# Grove_-_Base_Shield_for_IOIO-OTG.net
KiCad netlist of a schematic drawn in EAGLE
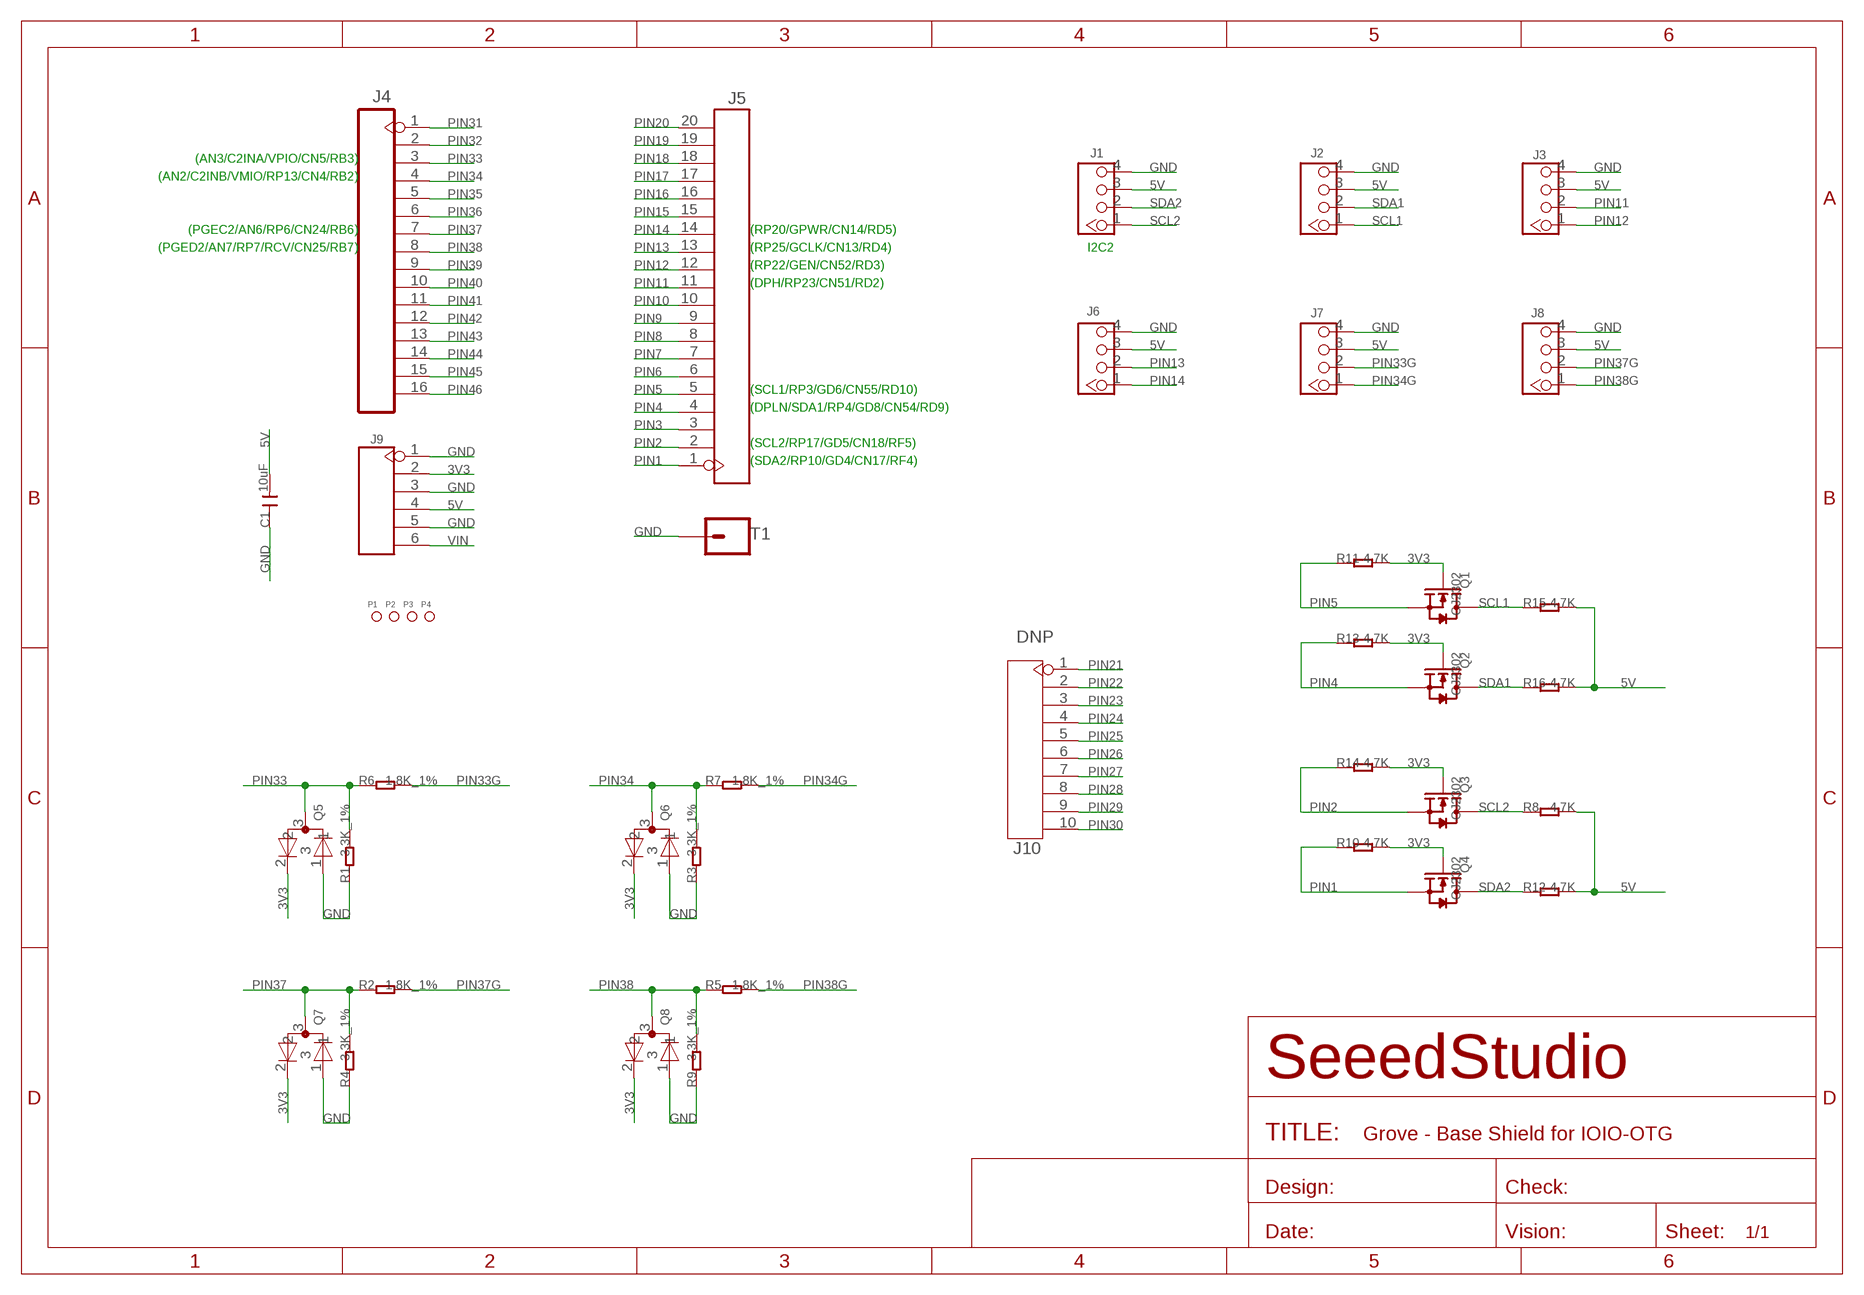
[diagram p0: schematic, sheet 1]

(export (version "E")
  (design (tool "Eeschema 10.0.6"))
  (components
    (comp (ref "C1")
      (value "10uF")
      (footprint "eagle-import:C0805")
      (libsource (lib "eagle-import") (part "C-0805"))
    )
    (comp (ref "J1")
      (value "TWIG-4P-2.0-2.0")
      (footprint "eagle-import:4P-2.0")
      (libsource (lib "eagle-import") (part "TWIG-4P-2.0-2.0"))
    )
    (comp (ref "J2")
      (value "TWIG-4P-2.0-2.0")
      (footprint "eagle-import:4P-2.0")
      (libsource (lib "eagle-import") (part "TWIG-4P-2.0-2.0"))
    )
    (comp (ref "J3")
      (value "TWIG-4P-2.0-2.0")
      (footprint "eagle-import:4P-2.0")
      (libsource (lib "eagle-import") (part "TWIG-4P-2.0-2.0"))
    )
    (comp (ref "J4")
      (value "HEADER-16P-2.54")
      (footprint "eagle-import:16P-2.54")
      (libsource (lib "eagle-import") (part "HEADER-16P-2.54"))
    )
    (comp (ref "J5")
      (value "HEADER-20P-2.54")
      (footprint "eagle-import:20P-2.54")
      (libsource (lib "eagle-import") (part "HEADER-20P-2.54"))
    )
    (comp (ref "J6")
      (value "TWIG-4P-2.0-2.0")
      (footprint "eagle-import:4P-2.0")
      (libsource (lib "eagle-import") (part "TWIG-4P-2.0-2.0"))
    )
    (comp (ref "J7")
      (value "TWIG-4P-2.0-2.0")
      (footprint "eagle-import:4P-2.0")
      (libsource (lib "eagle-import") (part "TWIG-4P-2.0-2.0"))
    )
    (comp (ref "J8")
      (value "TWIG-4P-2.0-2.0")
      (footprint "eagle-import:4P-2.0")
      (libsource (lib "eagle-import") (part "TWIG-4P-2.0-2.0"))
    )
    (comp (ref "J9")
      (value "HEADER-6P-65/35MIL")
      (footprint "eagle-import:6P-2.54-65_35MIL")
      (libsource (lib "eagle-import") (part "HEADER-6P-65/35MIL"))
    )
    (comp (ref "J10")
      (value "DNP")
      (footprint "eagle-import:10P-2.54")
      (libsource (lib "eagle-import") (part "HEADER-10P-2.54"))
    )
    (comp (ref "P1")
      (value "PAD-MARK")
      (footprint "eagle-import:ROUND-MARK-1.0")
      (fields (field (name "PARTNO") "DNP"))
      (libsource (lib "eagle-import") (part "PAD-MARK"))
    )
    (comp (ref "P2")
      (value "PAD-MARK")
      (footprint "eagle-import:ROUND-MARK-1.0")
      (fields (field (name "PARTNO") "DNP"))
      (libsource (lib "eagle-import") (part "PAD-MARK"))
    )
    (comp (ref "P3")
      (value "PAD-MARK")
      (footprint "eagle-import:ROUND-MARK-1.0")
      (fields (field (name "PARTNO") "DNP"))
      (libsource (lib "eagle-import") (part "PAD-MARK"))
    )
    (comp (ref "P4")
      (value "PAD-MARK")
      (footprint "eagle-import:ROUND-MARK-1.0")
      (fields (field (name "PARTNO") "DNP"))
      (libsource (lib "eagle-import") (part "PAD-MARK"))
    )
    (comp (ref "Q1")
      (value "CJ2302")
      (footprint "eagle-import:SOT23")
      (libsource (lib "eagle-import") (part "MOSFET-N'SOT23'"))
    )
    (comp (ref "Q2")
      (value "CJ2302")
      (footprint "eagle-import:SOT23")
      (libsource (lib "eagle-import") (part "MOSFET-N'SOT23'"))
    )
    (comp (ref "Q3")
      (value "CJ2302")
      (footprint "eagle-import:SOT23")
      (libsource (lib "eagle-import") (part "MOSFET-N'SOT23'"))
    )
    (comp (ref "Q4")
      (value "CJ2302")
      (footprint "eagle-import:SOT23")
      (libsource (lib "eagle-import") (part "MOSFET-N'SOT23'"))
    )
    (comp (ref "Q5")
      (value "BAV99")
      (footprint "eagle-import:SOT23")
      (libsource (lib "eagle-import") (part "BAV99"))
    )
    (comp (ref "Q6")
      (value "BAV99")
      (footprint "eagle-import:SOT23")
      (libsource (lib "eagle-import") (part "BAV99"))
    )
    (comp (ref "Q7")
      (value "BAV99")
      (footprint "eagle-import:SOT23")
      (libsource (lib "eagle-import") (part "BAV99"))
    )
    (comp (ref "Q8")
      (value "BAV99")
      (footprint "eagle-import:SOT23")
      (libsource (lib "eagle-import") (part "BAV99"))
    )
    (comp (ref "R1")
      (value "3.3K_1%")
      (footprint "eagle-import:R0603")
      (libsource (lib "eagle-import") (part "R-0603"))
    )
    (comp (ref "R2")
      (value "1.8K_1%")
      (footprint "eagle-import:R0603")
      (libsource (lib "eagle-import") (part "R-0603"))
    )
    (comp (ref "R3")
      (value "3.3K_1%")
      (footprint "eagle-import:R0603")
      (libsource (lib "eagle-import") (part "R-0603"))
    )
    (comp (ref "R4")
      (value "3.3K_1%")
      (footprint "eagle-import:R0603")
      (libsource (lib "eagle-import") (part "R-0603"))
    )
    (comp (ref "R5")
      (value "1.8K_1%")
      (footprint "eagle-import:R0603")
      (libsource (lib "eagle-import") (part "R-0603"))
    )
    (comp (ref "R6")
      (value "1.8K_1%")
      (footprint "eagle-import:R0603")
      (libsource (lib "eagle-import") (part "R-0603"))
    )
    (comp (ref "R7")
      (value "1.8K_1%")
      (footprint "eagle-import:R0603")
      (libsource (lib "eagle-import") (part "R-0603"))
    )
    (comp (ref "R8")
      (value "4.7K")
      (footprint "eagle-import:R0603")
      (libsource (lib "eagle-import") (part "R-0603"))
    )
    (comp (ref "R9")
      (value "3.3K_1%")
      (footprint "eagle-import:R0603")
      (libsource (lib "eagle-import") (part "R-0603"))
    )
    (comp (ref "R10")
      (value "4.7K")
      (footprint "eagle-import:R0603")
      (libsource (lib "eagle-import") (part "R-0603"))
    )
    (comp (ref "R11")
      (value "4.7K")
      (footprint "eagle-import:R0603")
      (libsource (lib "eagle-import") (part "R-0603"))
    )
    (comp (ref "R12")
      (value "4.7K")
      (footprint "eagle-import:R0603")
      (libsource (lib "eagle-import") (part "R-0603"))
    )
    (comp (ref "R13")
      (value "4.7K")
      (footprint "eagle-import:R0603")
      (libsource (lib "eagle-import") (part "R-0603"))
    )
    (comp (ref "R14")
      (value "4.7K")
      (footprint "eagle-import:R0603")
      (libsource (lib "eagle-import") (part "R-0603"))
    )
    (comp (ref "R15")
      (value "4.7K")
      (footprint "eagle-import:R0603")
      (libsource (lib "eagle-import") (part "R-0603"))
    )
    (comp (ref "R16")
      (value "4.7K")
      (footprint "eagle-import:R0603")
      (libsource (lib "eagle-import") (part "R-0603"))
    )
    (comp (ref "T1")
      (value "SPARKFUN_M01PTH")
      (footprint "eagle-import:SPARKFUN_1X01")
      (libsource (lib "eagle-import") (part "SPARKFUN_M01PTH"))
    )
  )
  (nets
    (net (code "1") (name "/3V3") (class "Default")
      (node (ref "J9") (pin "2") (pinfunction "2_2") (pintype "bidirectional"))
      (node (ref "Q1") (pin "1") (pinfunction "G_1") (pintype "passive"))
      (node (ref "Q2") (pin "1") (pinfunction "G_1") (pintype "passive"))
      (node (ref "Q3") (pin "1") (pinfunction "G_1") (pintype "passive"))
      (node (ref "Q4") (pin "1") (pinfunction "G_1") (pintype "passive"))
      (node (ref "Q5") (pin "2") (pinfunction "2_2") (pintype "bidirectional"))
      (node (ref "Q6") (pin "2") (pinfunction "2_2") (pintype "bidirectional"))
      (node (ref "Q7") (pin "2") (pinfunction "2_2") (pintype "bidirectional"))
      (node (ref "Q8") (pin "2") (pinfunction "2_2") (pintype "bidirectional"))
      (node (ref "R10") (pin "2") (pinfunction "2_2") (pintype "passive"))
      (node (ref "R11") (pin "2") (pinfunction "2_2") (pintype "passive"))
      (node (ref "R13") (pin "2") (pinfunction "2_2") (pintype "passive"))
      (node (ref "R14") (pin "2") (pinfunction "2_2") (pintype "passive"))
    )
    (net (code "2") (name "/5V") (class "Default")
      (node (ref "C1") (pin "2") (pinfunction "2_2") (pintype "passive"))
      (node (ref "J1") (pin "3") (pinfunction "3_3") (pintype "bidirectional"))
      (node (ref "J2") (pin "3") (pinfunction "3_3") (pintype "bidirectional"))
      (node (ref "J3") (pin "3") (pinfunction "3_3") (pintype "bidirectional"))
      (node (ref "J6") (pin "3") (pinfunction "3_3") (pintype "bidirectional"))
      (node (ref "J7") (pin "3") (pinfunction "3_3") (pintype "bidirectional"))
      (node (ref "J8") (pin "3") (pinfunction "3_3") (pintype "bidirectional"))
      (node (ref "J9") (pin "4") (pinfunction "4_4") (pintype "bidirectional"))
      (node (ref "R12") (pin "2") (pinfunction "2_2") (pintype "passive"))
      (node (ref "R15") (pin "2") (pinfunction "2_2") (pintype "passive"))
      (node (ref "R16") (pin "2") (pinfunction "2_2") (pintype "passive"))
      (node (ref "R8") (pin "2") (pinfunction "2_2") (pintype "passive"))
    )
    (net (code "3") (name "/GND") (class "Default")
      (node (ref "C1") (pin "1") (pinfunction "1_1") (pintype "passive"))
      (node (ref "J1") (pin "4") (pinfunction "4_4") (pintype "bidirectional"))
      (node (ref "J2") (pin "4") (pinfunction "4_4") (pintype "bidirectional"))
      (node (ref "J3") (pin "4") (pinfunction "4_4") (pintype "bidirectional"))
      (node (ref "J6") (pin "4") (pinfunction "4_4") (pintype "bidirectional"))
      (node (ref "J7") (pin "4") (pinfunction "4_4") (pintype "bidirectional"))
      (node (ref "J8") (pin "4") (pinfunction "4_4") (pintype "bidirectional"))
      (node (ref "J9") (pin "1") (pinfunction "1_1") (pintype "bidirectional"))
      (node (ref "J9") (pin "3") (pinfunction "3_3") (pintype "bidirectional"))
      (node (ref "J9") (pin "5") (pinfunction "5_5") (pintype "bidirectional"))
      (node (ref "Q5") (pin "1") (pinfunction "1_1") (pintype "bidirectional"))
      (node (ref "Q6") (pin "1") (pinfunction "1_1") (pintype "bidirectional"))
      (node (ref "Q7") (pin "1") (pinfunction "1_1") (pintype "bidirectional"))
      (node (ref "Q8") (pin "1") (pinfunction "1_1") (pintype "bidirectional"))
      (node (ref "R1") (pin "1") (pinfunction "1_1") (pintype "passive"))
      (node (ref "R3") (pin "1") (pinfunction "1_1") (pintype "passive"))
      (node (ref "R4") (pin "1") (pinfunction "1_1") (pintype "passive"))
      (node (ref "R9") (pin "1") (pinfunction "1_1") (pintype "passive"))
      (node (ref "T1") (pin "1") (pinfunction "1_1") (pintype "passive"))
    )
    (net (code "4") (name "/PIN1") (class "Default")
      (node (ref "J5") (pin "1") (pinfunction "P$1_1") (pintype "bidirectional"))
      (node (ref "Q4") (pin "2") (pinfunction "S_2") (pintype "passive"))
      (node (ref "R10") (pin "1") (pinfunction "1_1") (pintype "passive"))
    )
    (net (code "5") (name "/PIN2") (class "Default")
      (node (ref "J5") (pin "2") (pinfunction "P$2_2") (pintype "bidirectional"))
      (node (ref "Q3") (pin "2") (pinfunction "S_2") (pintype "passive"))
      (node (ref "R14") (pin "1") (pinfunction "1_1") (pintype "passive"))
    )
    (net (code "6") (name "/PIN3") (class "Default")
      (node (ref "J5") (pin "3") (pinfunction "P$3_3") (pintype "bidirectional"))
    )
    (net (code "7") (name "/PIN4") (class "Default")
      (node (ref "J5") (pin "4") (pinfunction "P$4_4") (pintype "bidirectional"))
      (node (ref "Q2") (pin "2") (pinfunction "S_2") (pintype "passive"))
      (node (ref "R13") (pin "1") (pinfunction "1_1") (pintype "passive"))
    )
    (net (code "8") (name "/PIN5") (class "Default")
      (node (ref "J5") (pin "5") (pinfunction "P$5_5") (pintype "bidirectional"))
      (node (ref "Q1") (pin "2") (pinfunction "S_2") (pintype "passive"))
      (node (ref "R11") (pin "1") (pinfunction "1_1") (pintype "passive"))
    )
    (net (code "9") (name "/PIN6") (class "Default")
      (node (ref "J5") (pin "6") (pinfunction "P$6_6") (pintype "bidirectional"))
    )
    (net (code "10") (name "/PIN7") (class "Default")
      (node (ref "J5") (pin "7") (pinfunction "P$7_7") (pintype "bidirectional"))
    )
    (net (code "11") (name "/PIN8") (class "Default")
      (node (ref "J5") (pin "8") (pinfunction "P$8_8") (pintype "bidirectional"))
    )
    (net (code "12") (name "/PIN9") (class "Default")
      (node (ref "J5") (pin "9") (pinfunction "P$9_9") (pintype "bidirectional"))
    )
    (net (code "13") (name "/PIN10") (class "Default")
      (node (ref "J5") (pin "10") (pinfunction "P$10_10") (pintype "bidirectional"))
    )
    (net (code "14") (name "/PIN11") (class "Default")
      (node (ref "J3") (pin "2") (pinfunction "2_2") (pintype "bidirectional"))
      (node (ref "J5") (pin "11") (pinfunction "P$11_11") (pintype "bidirectional"))
    )
    (net (code "15") (name "/PIN12") (class "Default")
      (node (ref "J3") (pin "1") (pinfunction "1_1") (pintype "bidirectional"))
      (node (ref "J5") (pin "12") (pinfunction "P$12_12") (pintype "bidirectional"))
    )
    (net (code "16") (name "/PIN13") (class "Default")
      (node (ref "J5") (pin "13") (pinfunction "P$13_13") (pintype "bidirectional"))
      (node (ref "J6") (pin "2") (pinfunction "2_2") (pintype "bidirectional"))
    )
    (net (code "17") (name "/PIN14") (class "Default")
      (node (ref "J5") (pin "14") (pinfunction "P$14_14") (pintype "bidirectional"))
      (node (ref "J6") (pin "1") (pinfunction "1_1") (pintype "bidirectional"))
    )
    (net (code "18") (name "/PIN15") (class "Default")
      (node (ref "J5") (pin "15") (pinfunction "P$15_15") (pintype "bidirectional"))
    )
    (net (code "19") (name "/PIN16") (class "Default")
      (node (ref "J5") (pin "16") (pinfunction "P$16_16") (pintype "bidirectional"))
    )
    (net (code "20") (name "/PIN17") (class "Default")
      (node (ref "J5") (pin "17") (pinfunction "P$17_17") (pintype "bidirectional"))
    )
    (net (code "21") (name "/PIN18") (class "Default")
      (node (ref "J5") (pin "18") (pinfunction "P$18_18") (pintype "bidirectional"))
    )
    (net (code "22") (name "/PIN19") (class "Default")
      (node (ref "J5") (pin "19") (pinfunction "P$19_19") (pintype "bidirectional"))
    )
    (net (code "23") (name "/PIN20") (class "Default")
      (node (ref "J5") (pin "20") (pinfunction "P$20_20") (pintype "bidirectional"))
    )
    (net (code "24") (name "/PIN21") (class "Default")
      (node (ref "J10") (pin "1") (pinfunction "1_1") (pintype "bidirectional"))
    )
    (net (code "25") (name "/PIN22") (class "Default")
      (node (ref "J10") (pin "2") (pinfunction "2_2") (pintype "bidirectional"))
    )
    (net (code "26") (name "/PIN23") (class "Default")
      (node (ref "J10") (pin "3") (pinfunction "3_3") (pintype "bidirectional"))
    )
    (net (code "27") (name "/PIN24") (class "Default")
      (node (ref "J10") (pin "4") (pinfunction "4_4") (pintype "bidirectional"))
    )
    (net (code "28") (name "/PIN25") (class "Default")
      (node (ref "J10") (pin "5") (pinfunction "5_5") (pintype "bidirectional"))
    )
    (net (code "29") (name "/PIN26") (class "Default")
      (node (ref "J10") (pin "6") (pinfunction "6_6") (pintype "bidirectional"))
    )
    (net (code "30") (name "/PIN27") (class "Default")
      (node (ref "J10") (pin "7") (pinfunction "7_7") (pintype "bidirectional"))
    )
    (net (code "31") (name "/PIN28") (class "Default")
      (node (ref "J10") (pin "8") (pinfunction "8_8") (pintype "bidirectional"))
    )
    (net (code "32") (name "/PIN29") (class "Default")
      (node (ref "J10") (pin "9") (pinfunction "9_9") (pintype "bidirectional"))
    )
    (net (code "33") (name "/PIN30") (class "Default")
      (node (ref "J10") (pin "10") (pinfunction "10_10") (pintype "bidirectional"))
    )
    (net (code "34") (name "/PIN31") (class "Default")
      (node (ref "J4") (pin "1") (pinfunction "1_1") (pintype "passive"))
    )
    (net (code "35") (name "/PIN32") (class "Default")
      (node (ref "J4") (pin "2") (pinfunction "2_2") (pintype "passive"))
    )
    (net (code "36") (name "/PIN33") (class "Default")
      (node (ref "J4") (pin "3") (pinfunction "3_3") (pintype "passive"))
      (node (ref "Q5") (pin "3") (pinfunction "3_3") (pintype "bidirectional"))
      (node (ref "R1") (pin "2") (pinfunction "2_2") (pintype "passive"))
      (node (ref "R6") (pin "1") (pinfunction "1_1") (pintype "passive"))
    )
    (net (code "37") (name "/PIN33G") (class "Default")
      (node (ref "J7") (pin "2") (pinfunction "2_2") (pintype "bidirectional"))
      (node (ref "R6") (pin "2") (pinfunction "2_2") (pintype "passive"))
    )
    (net (code "38") (name "/PIN34") (class "Default")
      (node (ref "J4") (pin "4") (pinfunction "4_4") (pintype "passive"))
      (node (ref "Q6") (pin "3") (pinfunction "3_3") (pintype "bidirectional"))
      (node (ref "R3") (pin "2") (pinfunction "2_2") (pintype "passive"))
      (node (ref "R7") (pin "1") (pinfunction "1_1") (pintype "passive"))
    )
    (net (code "39") (name "/PIN34G") (class "Default")
      (node (ref "J7") (pin "1") (pinfunction "1_1") (pintype "bidirectional"))
      (node (ref "R7") (pin "2") (pinfunction "2_2") (pintype "passive"))
    )
    (net (code "40") (name "/PIN35") (class "Default")
      (node (ref "J4") (pin "5") (pinfunction "5_5") (pintype "passive"))
    )
    (net (code "41") (name "/PIN36") (class "Default")
      (node (ref "J4") (pin "6") (pinfunction "6_6") (pintype "passive"))
    )
    (net (code "42") (name "/PIN37") (class "Default")
      (node (ref "J4") (pin "7") (pinfunction "7_7") (pintype "passive"))
      (node (ref "Q7") (pin "3") (pinfunction "3_3") (pintype "bidirectional"))
      (node (ref "R2") (pin "1") (pinfunction "1_1") (pintype "passive"))
      (node (ref "R4") (pin "2") (pinfunction "2_2") (pintype "passive"))
    )
    (net (code "43") (name "/PIN37G") (class "Default")
      (node (ref "J8") (pin "2") (pinfunction "2_2") (pintype "bidirectional"))
      (node (ref "R2") (pin "2") (pinfunction "2_2") (pintype "passive"))
    )
    (net (code "44") (name "/PIN38") (class "Default")
      (node (ref "J4") (pin "8") (pinfunction "8_8") (pintype "passive"))
      (node (ref "Q8") (pin "3") (pinfunction "3_3") (pintype "bidirectional"))
      (node (ref "R5") (pin "1") (pinfunction "1_1") (pintype "passive"))
      (node (ref "R9") (pin "2") (pinfunction "2_2") (pintype "passive"))
    )
    (net (code "45") (name "/PIN38G") (class "Default")
      (node (ref "J8") (pin "1") (pinfunction "1_1") (pintype "bidirectional"))
      (node (ref "R5") (pin "2") (pinfunction "2_2") (pintype "passive"))
    )
    (net (code "46") (name "/PIN39") (class "Default")
      (node (ref "J4") (pin "9") (pinfunction "9_9") (pintype "passive"))
    )
    (net (code "47") (name "/PIN40") (class "Default")
      (node (ref "J4") (pin "10") (pinfunction "10_10") (pintype "passive"))
    )
    (net (code "48") (name "/PIN41") (class "Default")
      (node (ref "J4") (pin "11") (pinfunction "11_11") (pintype "passive"))
    )
    (net (code "49") (name "/PIN42") (class "Default")
      (node (ref "J4") (pin "12") (pinfunction "12_12") (pintype "passive"))
    )
    (net (code "50") (name "/PIN43") (class "Default")
      (node (ref "J4") (pin "13") (pinfunction "13_13") (pintype "passive"))
    )
    (net (code "51") (name "/PIN44") (class "Default")
      (node (ref "J4") (pin "14") (pinfunction "14_14") (pintype "passive"))
    )
    (net (code "52") (name "/PIN45") (class "Default")
      (node (ref "J4") (pin "15") (pinfunction "15_15") (pintype "passive"))
    )
    (net (code "53") (name "/PIN46") (class "Default")
      (node (ref "J4") (pin "16") (pinfunction "16_16") (pintype "passive"))
    )
    (net (code "54") (name "/SCL1") (class "Default")
      (node (ref "J2") (pin "1") (pinfunction "1_1") (pintype "bidirectional"))
      (node (ref "Q1") (pin "3") (pinfunction "D_3") (pintype "passive"))
      (node (ref "R15") (pin "1") (pinfunction "1_1") (pintype "passive"))
    )
    (net (code "55") (name "/SCL2") (class "Default")
      (node (ref "J1") (pin "1") (pinfunction "1_1") (pintype "bidirectional"))
      (node (ref "Q3") (pin "3") (pinfunction "D_3") (pintype "passive"))
      (node (ref "R8") (pin "1") (pinfunction "1_1") (pintype "passive"))
    )
    (net (code "56") (name "/SDA1") (class "Default")
      (node (ref "J2") (pin "2") (pinfunction "2_2") (pintype "bidirectional"))
      (node (ref "Q2") (pin "3") (pinfunction "D_3") (pintype "passive"))
      (node (ref "R16") (pin "1") (pinfunction "1_1") (pintype "passive"))
    )
    (net (code "57") (name "/SDA2") (class "Default")
      (node (ref "J1") (pin "2") (pinfunction "2_2") (pintype "bidirectional"))
      (node (ref "Q4") (pin "3") (pinfunction "D_3") (pintype "passive"))
      (node (ref "R12") (pin "1") (pinfunction "1_1") (pintype "passive"))
    )
    (net (code "58") (name "/VIN") (class "Default")
      (node (ref "J9") (pin "6") (pinfunction "6_6") (pintype "bidirectional"))
    )
  )
)
